# SOT23-5.net
KiCad netlist of a schematic drawn in EAGLE
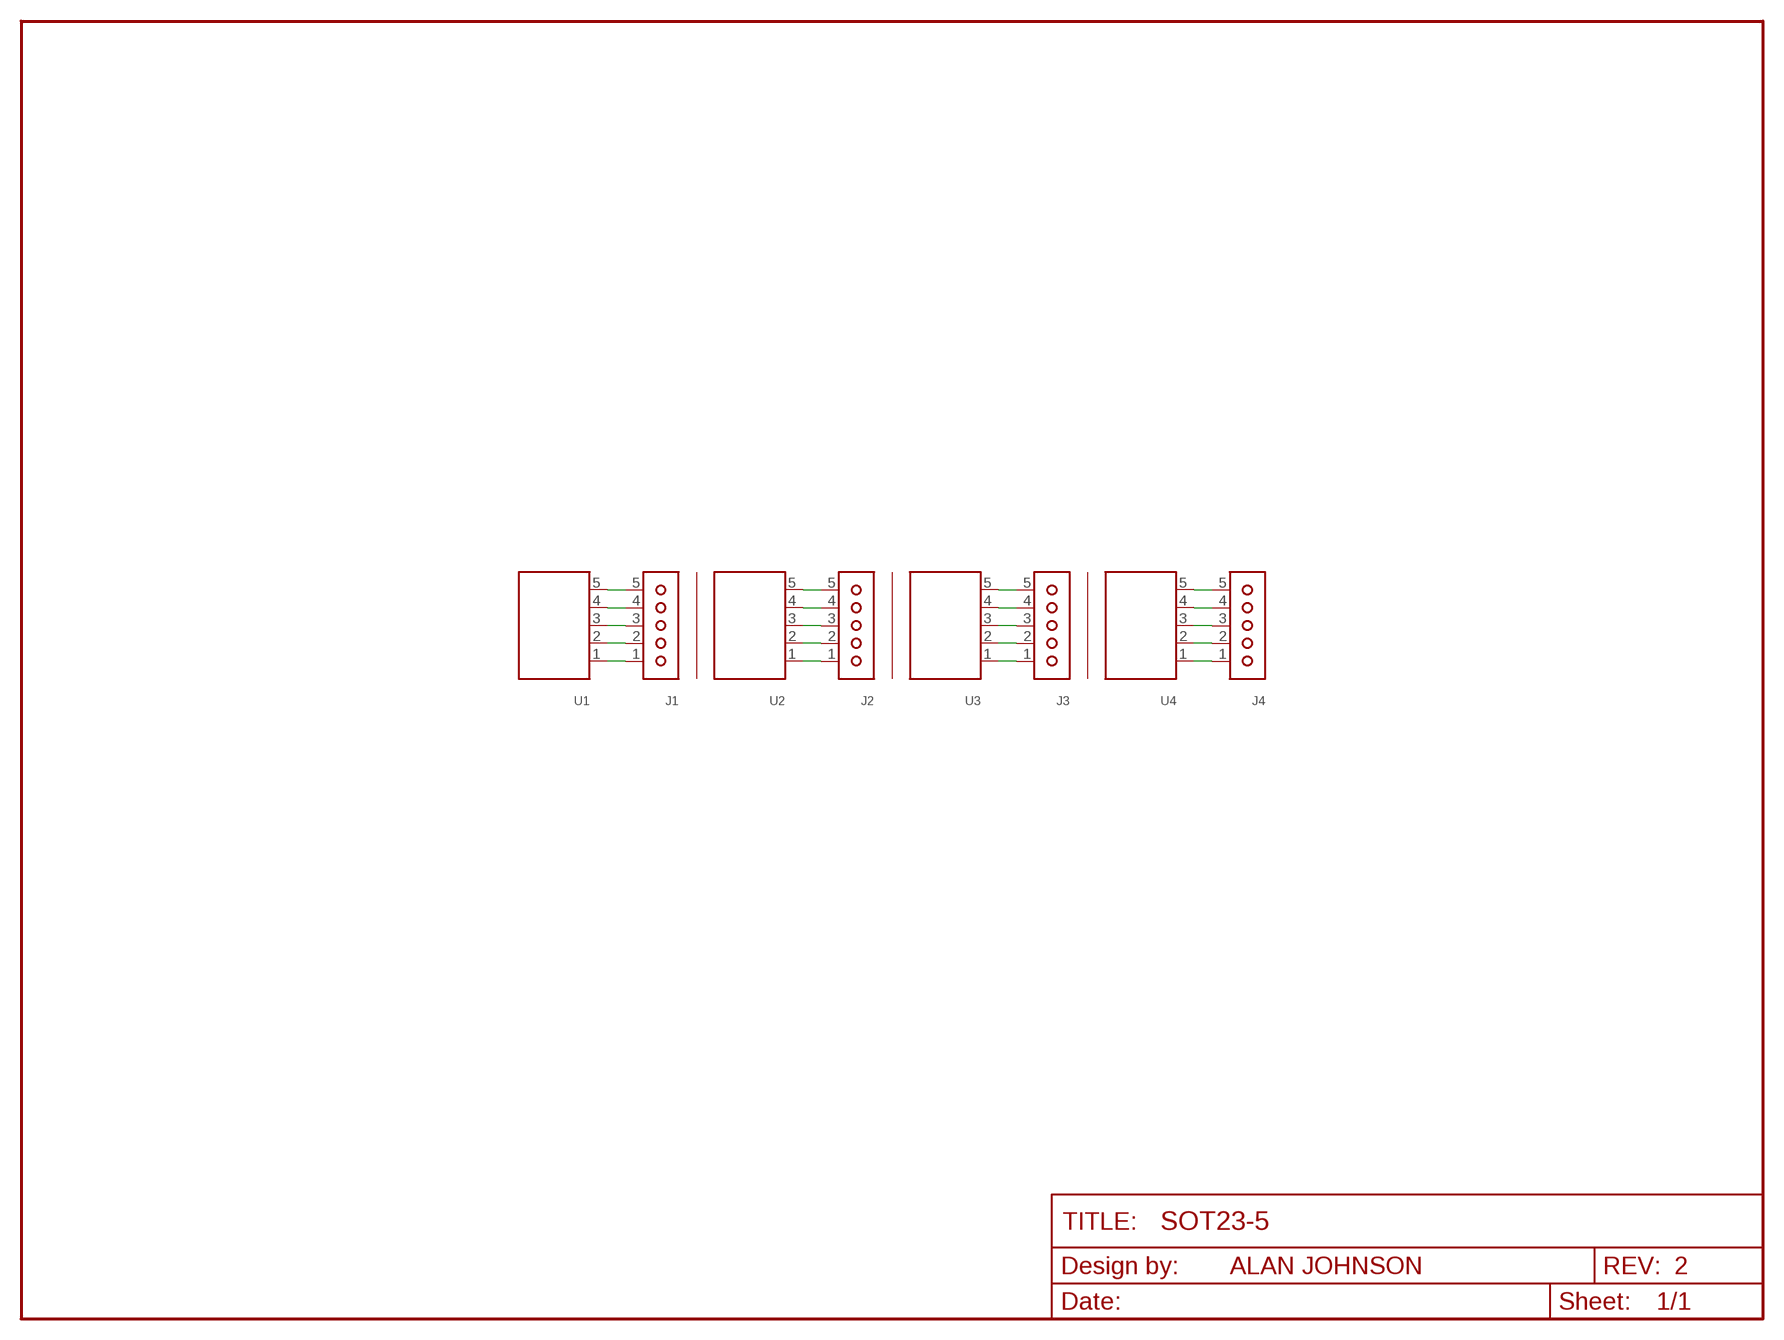
[diagram p0: schematic, sheet 1]

(export (version "E")
  (design (tool "Eeschema 10.0.6"))
  (components
    (comp (ref "J1")
      (value "1X05")
      (footprint "eagle-import:1X05")
      (libsource (lib "eagle-import") (part "1X05"))
    )
    (comp (ref "J2")
      (value "1X05")
      (footprint "eagle-import:1X05")
      (libsource (lib "eagle-import") (part "1X05"))
    )
    (comp (ref "J3")
      (value "1X05")
      (footprint "eagle-import:1X05")
      (libsource (lib "eagle-import") (part "1X05"))
    )
    (comp (ref "J4")
      (value "1X05")
      (footprint "eagle-import:1X05")
      (libsource (lib "eagle-import") (part "1X05"))
    )
    (comp (ref "U1")
      (value "SOT23-5")
      (footprint "eagle-import:SOT23-5")
      (libsource (lib "eagle-import") (part "SOT23-5"))
    )
    (comp (ref "U2")
      (value "SOT23-5")
      (footprint "eagle-import:SOT23-5")
      (libsource (lib "eagle-import") (part "SOT23-5"))
    )
    (comp (ref "U3")
      (value "SOT23-5")
      (footprint "eagle-import:SOT23-5")
      (libsource (lib "eagle-import") (part "SOT23-5"))
    )
    (comp (ref "U4")
      (value "SOT23-5")
      (footprint "eagle-import:SOT23-5")
      (libsource (lib "eagle-import") (part "SOT23-5"))
    )
  )
  (nets
    (net (code "1") (name "Net-(J1-Pad1)") (class "Default")
      (node (ref "J1") (pin "1") (pinfunction "1_1") (pintype "passive"))
      (node (ref "U1") (pin "1") (pinfunction "1_1") (pintype "passive"))
    )
    (net (code "2") (name "Net-(J1-Pad2)") (class "Default")
      (node (ref "J1") (pin "2") (pinfunction "2_2") (pintype "passive"))
      (node (ref "U1") (pin "2") (pinfunction "2_2") (pintype "passive"))
    )
    (net (code "3") (name "Net-(J1-Pad3)") (class "Default")
      (node (ref "J1") (pin "3") (pinfunction "3_3") (pintype "passive"))
      (node (ref "U1") (pin "3") (pinfunction "3_3") (pintype "passive"))
    )
    (net (code "4") (name "Net-(J1-Pad4)") (class "Default")
      (node (ref "J1") (pin "4") (pinfunction "4_4") (pintype "passive"))
      (node (ref "U1") (pin "4") (pinfunction "4_4") (pintype "passive"))
    )
    (net (code "5") (name "Net-(J1-Pad5)") (class "Default")
      (node (ref "J1") (pin "5") (pinfunction "5_5") (pintype "passive"))
      (node (ref "U1") (pin "5") (pinfunction "5_5") (pintype "passive"))
    )
    (net (code "6") (name "Net-(J2-Pad1)") (class "Default")
      (node (ref "J2") (pin "1") (pinfunction "1_1") (pintype "passive"))
      (node (ref "U2") (pin "1") (pinfunction "1_1") (pintype "passive"))
    )
    (net (code "7") (name "Net-(J2-Pad2)") (class "Default")
      (node (ref "J2") (pin "2") (pinfunction "2_2") (pintype "passive"))
      (node (ref "U2") (pin "2") (pinfunction "2_2") (pintype "passive"))
    )
    (net (code "8") (name "Net-(J2-Pad3)") (class "Default")
      (node (ref "J2") (pin "3") (pinfunction "3_3") (pintype "passive"))
      (node (ref "U2") (pin "3") (pinfunction "3_3") (pintype "passive"))
    )
    (net (code "9") (name "Net-(J2-Pad4)") (class "Default")
      (node (ref "J2") (pin "4") (pinfunction "4_4") (pintype "passive"))
      (node (ref "U2") (pin "4") (pinfunction "4_4") (pintype "passive"))
    )
    (net (code "10") (name "Net-(J2-Pad5)") (class "Default")
      (node (ref "J2") (pin "5") (pinfunction "5_5") (pintype "passive"))
      (node (ref "U2") (pin "5") (pinfunction "5_5") (pintype "passive"))
    )
    (net (code "11") (name "Net-(J3-Pad1)") (class "Default")
      (node (ref "J3") (pin "1") (pinfunction "1_1") (pintype "passive"))
      (node (ref "U3") (pin "1") (pinfunction "1_1") (pintype "passive"))
    )
    (net (code "12") (name "Net-(J3-Pad2)") (class "Default")
      (node (ref "J3") (pin "2") (pinfunction "2_2") (pintype "passive"))
      (node (ref "U3") (pin "2") (pinfunction "2_2") (pintype "passive"))
    )
    (net (code "13") (name "Net-(J3-Pad3)") (class "Default")
      (node (ref "J3") (pin "3") (pinfunction "3_3") (pintype "passive"))
      (node (ref "U3") (pin "3") (pinfunction "3_3") (pintype "passive"))
    )
    (net (code "14") (name "Net-(J3-Pad4)") (class "Default")
      (node (ref "J3") (pin "4") (pinfunction "4_4") (pintype "passive"))
      (node (ref "U3") (pin "4") (pinfunction "4_4") (pintype "passive"))
    )
    (net (code "15") (name "Net-(J3-Pad5)") (class "Default")
      (node (ref "J3") (pin "5") (pinfunction "5_5") (pintype "passive"))
      (node (ref "U3") (pin "5") (pinfunction "5_5") (pintype "passive"))
    )
    (net (code "16") (name "Net-(J4-Pad1)") (class "Default")
      (node (ref "J4") (pin "1") (pinfunction "1_1") (pintype "passive"))
      (node (ref "U4") (pin "1") (pinfunction "1_1") (pintype "passive"))
    )
    (net (code "17") (name "Net-(J4-Pad2)") (class "Default")
      (node (ref "J4") (pin "2") (pinfunction "2_2") (pintype "passive"))
      (node (ref "U4") (pin "2") (pinfunction "2_2") (pintype "passive"))
    )
    (net (code "18") (name "Net-(J4-Pad3)") (class "Default")
      (node (ref "J4") (pin "3") (pinfunction "3_3") (pintype "passive"))
      (node (ref "U4") (pin "3") (pinfunction "3_3") (pintype "passive"))
    )
    (net (code "19") (name "Net-(J4-Pad4)") (class "Default")
      (node (ref "J4") (pin "4") (pinfunction "4_4") (pintype "passive"))
      (node (ref "U4") (pin "4") (pinfunction "4_4") (pintype "passive"))
    )
    (net (code "20") (name "Net-(J4-Pad5)") (class "Default")
      (node (ref "J4") (pin "5") (pinfunction "5_5") (pintype "passive"))
      (node (ref "U4") (pin "5") (pinfunction "5_5") (pintype "passive"))
    )
  )
)
